# freezeTime.net
KiCad netlist of a schematic drawn in EAGLE
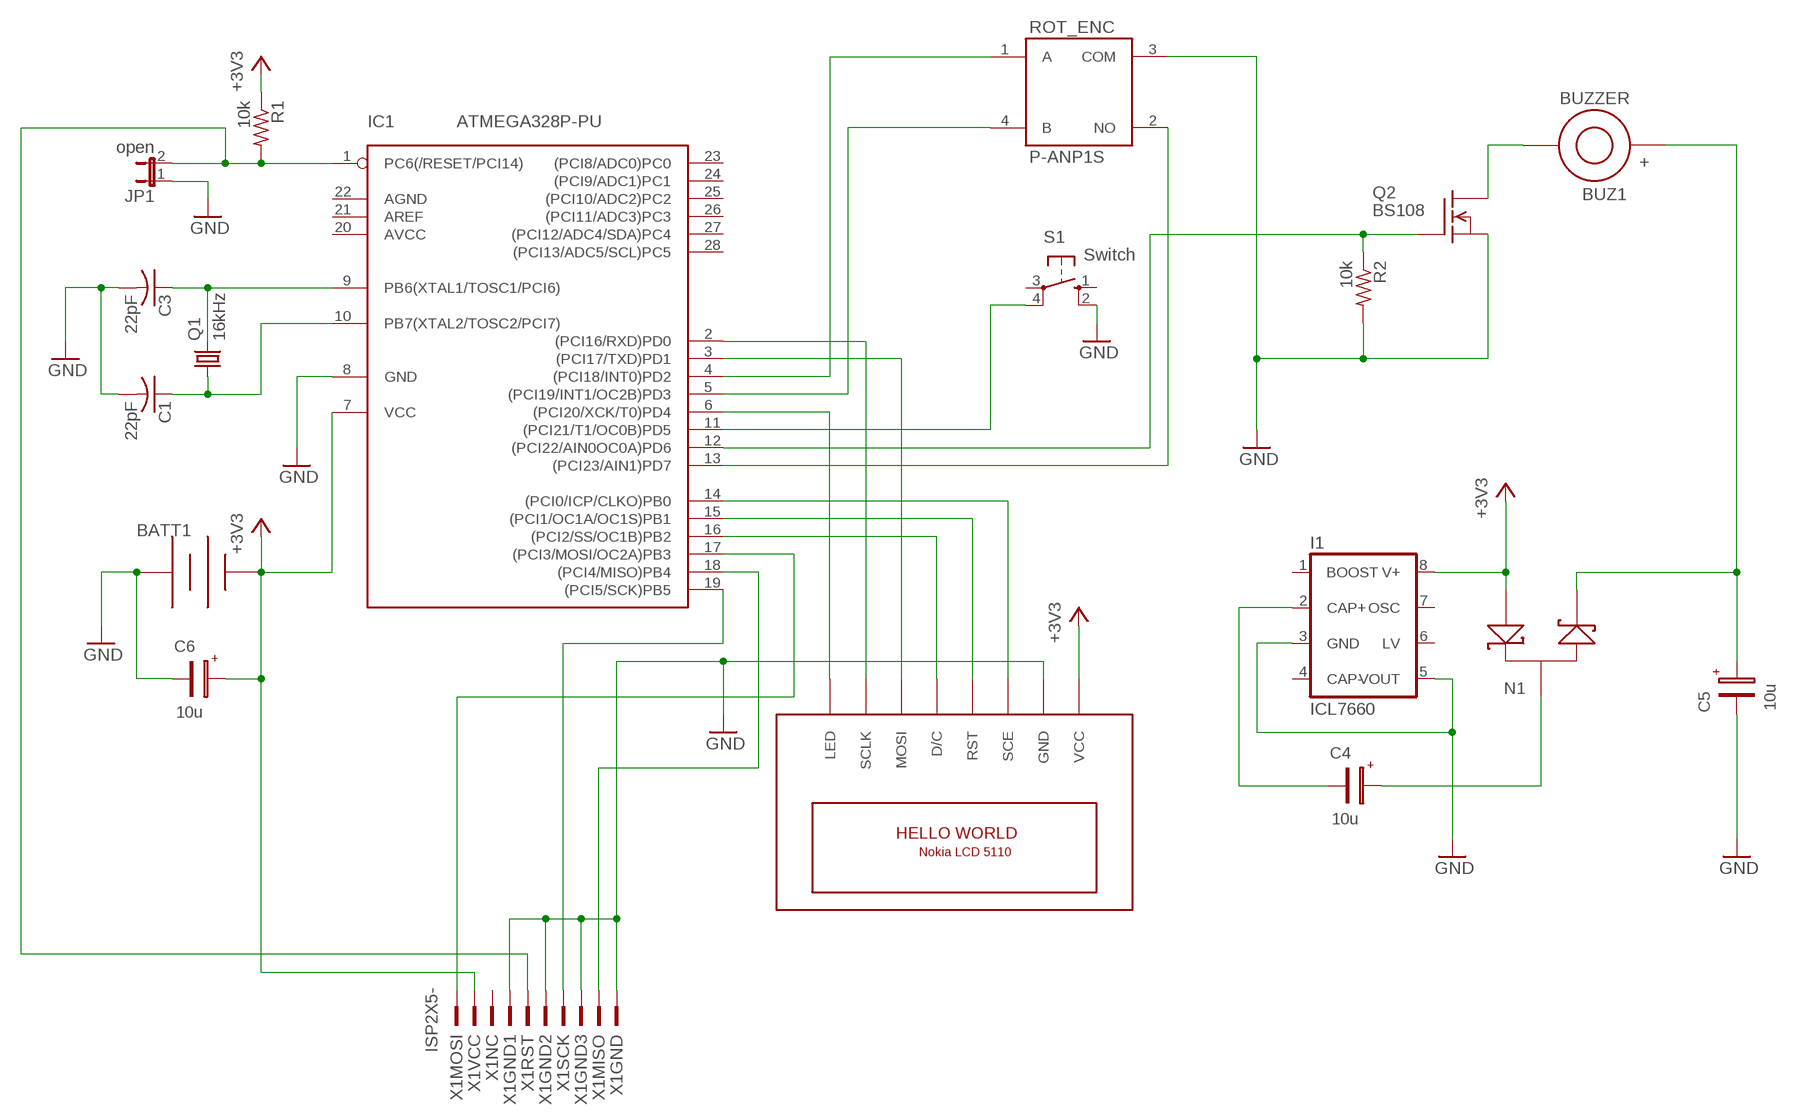
[diagram p0: schematic, sheet 1]

(export (version "E")
  (design (tool "Eeschema 10.0.6"))
  (components
    (comp (ref "BATT1")
      (value "3VBATTERY")
      (footprint "eagle-import:BH241-3A")
      (libsource (lib "eagle-import") (part "3VBATTERY"))
    )
    (comp (ref "BUZ1")
      (value "BUZZER")
      (footprint "eagle-import:AL1210MTE-P5R")
      (libsource (lib "eagle-import") (part "BUZZER"))
    )
    (comp (ref "C1")
      (value "22pF")
      (footprint "eagle-import:C1206")
      (libsource (lib "eagle-import") (part "C-USC1206"))
    )
    (comp (ref "C3")
      (value "22pF")
      (footprint "eagle-import:C1206")
      (libsource (lib "eagle-import") (part "C-USC1206"))
    )
    (comp (ref "C4")
      (value "10u")
      (footprint "eagle-import:C_6032-28R")
      (libsource (lib "eagle-import") (part "C-TANCTS"))
    )
    (comp (ref "C5")
      (value "10u")
      (footprint "eagle-import:C_6032-28R")
      (libsource (lib "eagle-import") (part "C-TANCTS"))
    )
    (comp (ref "C6")
      (value "10u")
      (footprint "eagle-import:C_6032-28R")
      (libsource (lib "eagle-import") (part "C-TANCTS"))
    )
    (comp (ref "I1")
      (value "ICL7660")
      (footprint "eagle-import:SO08")
      (libsource (lib "eagle-import") (part "ICL7660S7660SCBA"))
    )
    (comp (ref "IC1")
      (value "ATMEGA328P-PU")
      (footprint "eagle-import:DIL28-3")
      (libsource (lib "eagle-import") (part "ATMEGA168P-20"))
    )
    (comp (ref "JP1")
      (value "open")
      (footprint "eagle-import:JP1")
      (libsource (lib "eagle-import") (part "JP1E"))
    )
    (comp (ref "LCD1")
      (value "LCD_NOKIA5110")
      (footprint "eagle-import:LCD_NOKIA5110")
      (libsource (lib "eagle-import") (part "LCD_NOKIA5110"))
    )
    (comp (ref "N1")
      (value "BAT54S")
      (footprint "eagle-import:SOT23")
      (libsource (lib "eagle-import") (part "BAT54SBAT54S"))
    )
    (comp (ref "Q1")
      (value "16kHz")
      (footprint "eagle-import:HC49U70")
      (libsource (lib "eagle-import") (part "CRYSTALHC49U70"))
    )
    (comp (ref "Q2")
      (value "BS108")
      (footprint "eagle-import:TO92-INLINE")
      (libsource (lib "eagle-import") (part "FQN1N50CI"))
    )
    (comp (ref "R1")
      (value "10k")
      (footprint "eagle-import:R1206")
      (libsource (lib "eagle-import") (part "R-US_R1206"))
    )
    (comp (ref "R2")
      (value "10k")
      (footprint "eagle-import:R1206")
      (libsource (lib "eagle-import") (part "R-US_R1206"))
    )
    (comp (ref "ROT_ENC")
      (value "P-ANP1S")
      (footprint "eagle-import:P-ANP1S")
      (libsource (lib "eagle-import") (part "P-ANP1SP-ANP1S"))
    )
    (comp (ref "S1")
      (value "Switch")
      (footprint "eagle-import:TACTS-24N")
      (fields (field (name "MF") "NINIGI"))
      (libsource (lib "eagle-import") (part "SPST_SWITCH"))
    )
    (comp (ref "X1")
      (value "ISP2X5-")
      (footprint "eagle-import:PAK100_2500-10")
      (fields (field (name "MF") "3M") (field (name "MPN") "2510-6002UB"))
      (libsource (lib "eagle-import") (part "ISP2X5-"))
    )
  )
  (nets
    (net (code "1") (name "+3V3") (class "Default")
      (node (ref "BATT1") (pin "+") (pinfunction "+_+") (pintype "bidirectional"))
      (node (ref "C6") (pin "+") (pinfunction "P$1_+") (pintype "passive"))
      (node (ref "I1") (pin "8") (pinfunction "V+_8") (pintype "power_in"))
      (node (ref "IC1") (pin "7") (pinfunction "VCC_7") (pintype "bidirectional"))
      (node (ref "LCD1") (pin "P$1") (pinfunction "VCC_P$1") (pintype "power_in"))
      (node (ref "N1") (pin "1") (pinfunction "P$2_1") (pintype "passive"))
      (node (ref "R1") (pin "1") (pinfunction "1_1") (pintype "passive"))
      (node (ref "X1") (pin "2") (pinfunction "KL_2") (pintype "passive"))
    )
    (net (code "2") (name "GND") (class "Default")
      (node (ref "BATT1") (pin "-") (pinfunction "-_-") (pintype "bidirectional"))
      (node (ref "C1") (pin "2") (pinfunction "2_2") (pintype "passive"))
      (node (ref "C3") (pin "2") (pinfunction "2_2") (pintype "passive"))
      (node (ref "C5") (pin "-") (pinfunction "P$2_-") (pintype "passive"))
      (node (ref "C6") (pin "-") (pinfunction "P$2_-") (pintype "passive"))
      (node (ref "I1") (pin "3") (pinfunction "GND_3") (pintype "power_in"))
      (node (ref "I1") (pin "5") (pinfunction "VOUT_5") (pintype "output"))
      (node (ref "IC1") (pin "8") (pinfunction "GND_8") (pintype "bidirectional"))
      (node (ref "JP1") (pin "1") (pinfunction "1_1") (pintype "passive"))
      (node (ref "LCD1") (pin "P$2") (pinfunction "GND_P$2") (pintype "power_in"))
      (node (ref "Q2") (pin "3") (pinfunction "S_3") (pintype "passive"))
      (node (ref "R2") (pin "2") (pinfunction "2_2") (pintype "passive"))
      (node (ref "ROT_ENC") (pin "3") (pinfunction "COM_3") (pintype "bidirectional"))
      (node (ref "S1") (pin "2") (pinfunction "S1_2") (pintype "passive"))
      (node (ref "X1") (pin "10") (pinfunction "KL_10") (pintype "passive"))
      (node (ref "X1") (pin "4") (pinfunction "KL_4") (pintype "passive"))
      (node (ref "X1") (pin "6") (pinfunction "KL_6") (pintype "passive"))
      (node (ref "X1") (pin "8") (pinfunction "KL_8") (pintype "passive"))
    )
    (net (code "3") (name "Net-(BUZ1-+)") (class "Default")
      (node (ref "BUZ1") (pin "1") (pinfunction "+_1") (pintype "bidirectional"))
      (node (ref "C5") (pin "+") (pinfunction "P$1_+") (pintype "passive"))
      (node (ref "N1") (pin "2") (pinfunction "P$3_2") (pintype "passive"))
    )
    (net (code "4") (name "Net-(BUZ1-P$2)") (class "Default")
      (node (ref "BUZ1") (pin "2") (pinfunction "P$2_2") (pintype "bidirectional"))
      (node (ref "Q2") (pin "1") (pinfunction "D_1") (pintype "passive"))
    )
    (net (code "5") (name "Net-(C4-P$1)") (class "Default")
      (node (ref "C4") (pin "+") (pinfunction "P$1_+") (pintype "passive"))
      (node (ref "N1") (pin "3") (pinfunction "P$1_3") (pintype "passive"))
    )
    (net (code "6") (name "Net-(C4-P$2)") (class "Default")
      (node (ref "C4") (pin "-") (pinfunction "P$2_-") (pintype "passive"))
      (node (ref "I1") (pin "2") (pinfunction "CAP+_2") (pintype "bidirectional"))
    )
    (net (code "7") (name "Net-(IC1-(PCI0{slash}ICP{slash}CLKO)PB0)") (class "Default")
      (node (ref "IC1") (pin "14") (pinfunction "(PCI0/ICP/CLKO)PB0_14") (pintype "bidirectional"))
      (node (ref "LCD1") (pin "P$3") (pinfunction "SCE_P$3") (pintype "bidirectional"))
    )
    (net (code "8") (name "Net-(IC1-(PCI1{slash}OC1A{slash}OC1S)PB1)") (class "Default")
      (node (ref "IC1") (pin "15") (pinfunction "(PCI1/OC1A/OC1S)PB1_15") (pintype "bidirectional"))
      (node (ref "LCD1") (pin "P$4") (pinfunction "RST_P$4") (pintype "bidirectional"))
    )
    (net (code "9") (name "Net-(IC1-(PCI2{slash}SS{slash}OC1B)PB2)") (class "Default")
      (node (ref "IC1") (pin "16") (pinfunction "(PCI2/SS/OC1B)PB2_16") (pintype "bidirectional"))
      (node (ref "LCD1") (pin "P$5") (pinfunction "D/C_P$5") (pintype "bidirectional"))
    )
    (net (code "10") (name "Net-(IC1-(PCI3{slash}MOSI{slash}OC2A)PB3)") (class "Default")
      (node (ref "IC1") (pin "17") (pinfunction "(PCI3/MOSI/OC2A)PB3_17") (pintype "bidirectional"))
      (node (ref "X1") (pin "1") (pinfunction "KL_1") (pintype "passive"))
    )
    (net (code "11") (name "Net-(IC1-(PCI4{slash}MISO)PB4)") (class "Default")
      (node (ref "IC1") (pin "18") (pinfunction "(PCI4/MISO)PB4_18") (pintype "bidirectional"))
      (node (ref "X1") (pin "9") (pinfunction "KL_9") (pintype "passive"))
    )
    (net (code "12") (name "Net-(IC1-(PCI5{slash}SCK)PB5)") (class "Default")
      (node (ref "IC1") (pin "19") (pinfunction "(PCI5/SCK)PB5_19") (pintype "bidirectional"))
      (node (ref "X1") (pin "7") (pinfunction "KL_7") (pintype "passive"))
    )
    (net (code "13") (name "Net-(IC1-(PCI16{slash}RXD)PD0)") (class "Default")
      (node (ref "IC1") (pin "2") (pinfunction "(PCI16/RXD)PD0_2") (pintype "bidirectional"))
      (node (ref "LCD1") (pin "P$7") (pinfunction "SCLK_P$7") (pintype "bidirectional"))
    )
    (net (code "14") (name "Net-(IC1-(PCI17{slash}TXD)PD1)") (class "Default")
      (node (ref "IC1") (pin "3") (pinfunction "(PCI17/TXD)PD1_3") (pintype "bidirectional"))
      (node (ref "LCD1") (pin "P$6") (pinfunction "MOSI_P$6") (pintype "bidirectional"))
    )
    (net (code "15") (name "Net-(IC1-(PCI18{slash}INT0)PD2)") (class "Default")
      (node (ref "IC1") (pin "4") (pinfunction "(PCI18/INT0)PD2_4") (pintype "bidirectional"))
      (node (ref "ROT_ENC") (pin "1") (pinfunction "A_1") (pintype "bidirectional"))
    )
    (net (code "16") (name "Net-(IC1-(PCI19{slash}INT1{slash}OC2B)PD3)") (class "Default")
      (node (ref "IC1") (pin "5") (pinfunction "(PCI19/INT1/OC2B)PD3_5") (pintype "bidirectional"))
      (node (ref "ROT_ENC") (pin "4") (pinfunction "B_4") (pintype "bidirectional"))
    )
    (net (code "17") (name "Net-(IC1-(PCI20{slash}XCK{slash}T0)PD4)") (class "Default")
      (node (ref "IC1") (pin "6") (pinfunction "(PCI20/XCK/T0)PD4_6") (pintype "bidirectional"))
      (node (ref "LCD1") (pin "P$8") (pinfunction "LED_P$8") (pintype "bidirectional"))
    )
    (net (code "18") (name "Net-(IC1-(PCI21{slash}T1{slash}OC0B)PD5)") (class "Default")
      (node (ref "IC1") (pin "11") (pinfunction "(PCI21/T1/OC0B)PD5_11") (pintype "bidirectional"))
      (node (ref "S1") (pin "4") (pinfunction "P1_4") (pintype "passive"))
    )
    (net (code "19") (name "Net-(IC1-(PCI22{slash}AIN0OC0A)PD6)") (class "Default")
      (node (ref "IC1") (pin "12") (pinfunction "(PCI22/AIN0OC0A)PD6_12") (pintype "bidirectional"))
      (node (ref "Q2") (pin "2") (pinfunction "G_2") (pintype "passive"))
      (node (ref "R2") (pin "1") (pinfunction "1_1") (pintype "passive"))
    )
    (net (code "20") (name "Net-(IC1-(PCI23{slash}AIN1)PD7)") (class "Default")
      (node (ref "IC1") (pin "13") (pinfunction "(PCI23/AIN1)PD7_13") (pintype "bidirectional"))
      (node (ref "ROT_ENC") (pin "2") (pinfunction "NO_2") (pintype "bidirectional"))
    )
    (net (code "21") (name "Net-(IC1-PB6(XTAL1{slash}TOSC1{slash}PCI6))") (class "Default")
      (node (ref "C3") (pin "1") (pinfunction "1_1") (pintype "passive"))
      (node (ref "IC1") (pin "9") (pinfunction "PB6(XTAL1/TOSC1/PCI6)_9") (pintype "bidirectional"))
      (node (ref "Q1") (pin "2") (pinfunction "2_2") (pintype "passive"))
    )
    (net (code "22") (name "Net-(IC1-PB7(XTAL2{slash}TOSC2{slash}PCI7))") (class "Default")
      (node (ref "C1") (pin "1") (pinfunction "1_1") (pintype "passive"))
      (node (ref "IC1") (pin "10") (pinfunction "PB7(XTAL2/TOSC2/PCI7)_10") (pintype "bidirectional"))
      (node (ref "Q1") (pin "1") (pinfunction "1_1") (pintype "passive"))
    )
    (net (code "23") (name "Net-(IC1-PC6({slash}RESET{slash}PCI14))") (class "Default")
      (node (ref "IC1") (pin "1") (pinfunction "PC6(/RESET/PCI14)_1") (pintype "bidirectional"))
      (node (ref "JP1") (pin "2") (pinfunction "2_2") (pintype "passive"))
      (node (ref "R1") (pin "2") (pinfunction "2_2") (pintype "passive"))
      (node (ref "X1") (pin "5") (pinfunction "KL_5") (pintype "passive"))
    )
    (net (code "24") (name "unconnected-(I1-BOOST-Pad1)") (class "Default")
      (node (ref "I1") (pin "1") (pinfunction "BOOST_1") (pintype "bidirectional"))
    )
    (net (code "25") (name "unconnected-(I1-CAP--Pad4)") (class "Default")
      (node (ref "I1") (pin "4") (pinfunction "CAP-_4") (pintype "bidirectional"))
    )
    (net (code "26") (name "unconnected-(I1-LV-Pad6)") (class "Default")
      (node (ref "I1") (pin "6") (pinfunction "LV_6") (pintype "bidirectional"))
    )
    (net (code "27") (name "unconnected-(I1-OSC-Pad7)") (class "Default")
      (node (ref "I1") (pin "7") (pinfunction "OSC_7") (pintype "bidirectional"))
    )
    (net (code "28") (name "unconnected-(IC1-(PCI8{slash}ADC0)PC0-Pad23)") (class "Default")
      (node (ref "IC1") (pin "23") (pinfunction "(PCI8/ADC0)PC0_23") (pintype "bidirectional"))
    )
    (net (code "29") (name "unconnected-(IC1-(PCI9{slash}ADC1)PC1-Pad24)") (class "Default")
      (node (ref "IC1") (pin "24") (pinfunction "(PCI9/ADC1)PC1_24") (pintype "bidirectional"))
    )
    (net (code "30") (name "unconnected-(IC1-(PCI10{slash}ADC2)PC2-Pad25)") (class "Default")
      (node (ref "IC1") (pin "25") (pinfunction "(PCI10/ADC2)PC2_25") (pintype "bidirectional"))
    )
    (net (code "31") (name "unconnected-(IC1-(PCI11{slash}ADC3)PC3-Pad26)") (class "Default")
      (node (ref "IC1") (pin "26") (pinfunction "(PCI11/ADC3)PC3_26") (pintype "bidirectional"))
    )
    (net (code "32") (name "unconnected-(IC1-(PCI12{slash}ADC4{slash}SDA)PC4-Pad27)") (class "Default")
      (node (ref "IC1") (pin "27") (pinfunction "(PCI12/ADC4/SDA)PC4_27") (pintype "bidirectional"))
    )
    (net (code "33") (name "unconnected-(IC1-(PCI13{slash}ADC5{slash}SCL)PC5-Pad28)") (class "Default")
      (node (ref "IC1") (pin "28") (pinfunction "(PCI13/ADC5/SCL)PC5_28") (pintype "bidirectional"))
    )
    (net (code "34") (name "unconnected-(IC1-AGND-Pad22)") (class "Default")
      (node (ref "IC1") (pin "22") (pinfunction "AGND_22") (pintype "bidirectional"))
    )
    (net (code "35") (name "unconnected-(IC1-AREF-Pad21)") (class "Default")
      (node (ref "IC1") (pin "21") (pinfunction "AREF_21") (pintype "bidirectional"))
    )
    (net (code "36") (name "unconnected-(IC1-AVCC-Pad20)") (class "Default")
      (node (ref "IC1") (pin "20") (pinfunction "AVCC_20") (pintype "bidirectional"))
    )
    (net (code "37") (name "unconnected-(S1-P-Pad3)") (class "Default")
      (node (ref "S1") (pin "3") (pinfunction "P_3") (pintype "passive"))
    )
    (net (code "38") (name "unconnected-(S1-S-Pad1)") (class "Default")
      (node (ref "S1") (pin "1") (pinfunction "S_1") (pintype "passive"))
    )
    (net (code "39") (name "unconnected-(X1G-KL-Pad3)") (class "Default")
      (node (ref "X1") (pin "3") (pinfunction "KL_3") (pintype "passive"))
    )
  )
)
